# Experiment_2.net
KiCad netlist of a schematic drawn in Altium Designer
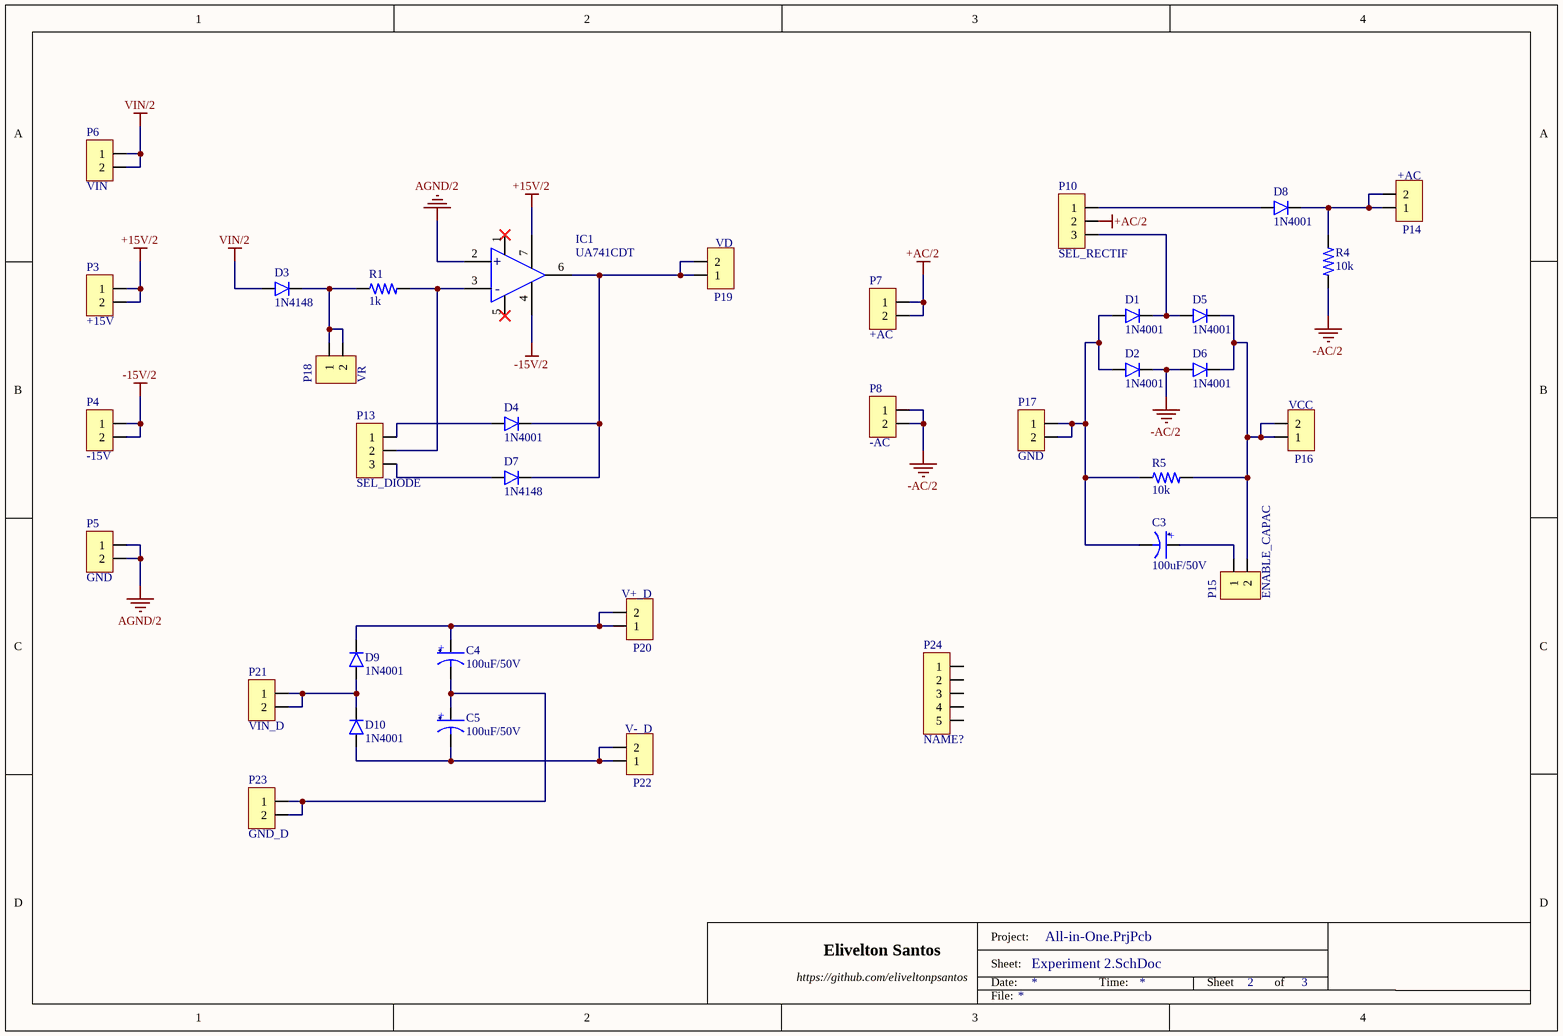
[diagram p0: Experiment 2.SchDoc]

(export (version "E")
  (design (tool "Eeschema 10.0.6"))
  (components
    (comp (ref "C3")
      (value "100uF/50V")
      (footprint "C-3.5x8")
      (description "CAP ALUM 100UF 20% 50V RADIAL")
      (fields
        (field (name "MANUFACTURER") "Nichicon")
        (field (name "MANUFACTURER PART NUMBER") "UVR1H101MPD")
      )
      (libsource (lib "Capacitors") (part "UVR1H101MPD"))
    )
    (comp (ref "C4")
      (value "100uF/50V")
      (footprint "C-3.5x8")
      (description "CAP ALUM 100UF 20% 50V RADIAL")
      (fields
        (field (name "MANUFACTURER") "Nichicon")
        (field (name "MANUFACTURER PART NUMBER") "UVR1H101MPD")
      )
      (libsource (lib "") (part "UVR1H101MPD_1"))
    )
    (comp (ref "C5")
      (value "100uF/50V")
      (footprint "C-3.5x8")
      (description "CAP ALUM 100UF 20% 50V RADIAL")
      (fields
        (field (name "MANUFACTURER") "Nichicon")
        (field (name "MANUFACTURER PART NUMBER") "UVR1H101MPD")
      )
      (libsource (lib "") (part "UVR1H101MPD_1"))
    )
    (comp (ref "D1")
      (value "1N4001")
      (footprint "DO41-10")
      (description "DIODE GEN PURP 50V 1A DO41")
      (fields (field (name "MANUFACTURER") "Fairchild Semiconductor"))
      (libsource (lib "Diodes") (part "1N4001"))
    )
    (comp (ref "D2")
      (value "1N4001")
      (footprint "DO41-10")
      (description "DIODE GEN PURP 50V 1A DO41")
      (fields (field (name "MANUFACTURER") "Fairchild Semiconductor"))
      (libsource (lib "Diodes") (part "1N4001"))
    )
    (comp (ref "D3")
      (value "1N4148")
      (footprint "DO35-10")
      (description "DIODE GEN PURP 100V 200MA DO35")
      (fields (field (name "MANUFACTURER") "Fairchild Semiconductor"))
      (libsource (lib "Diodes") (part "1N4148"))
    )
    (comp (ref "D4")
      (value "1N4001")
      (footprint "DO41-10")
      (description "DIODE GEN PURP 50V 1A DO41")
      (fields (field (name "MANUFACTURER") "Fairchild Semiconductor"))
      (libsource (lib "Diodes") (part "1N4001"))
    )
    (comp (ref "D5")
      (value "1N4001")
      (footprint "DO41-10")
      (description "DIODE GEN PURP 50V 1A DO41")
      (fields (field (name "MANUFACTURER") "Fairchild Semiconductor"))
      (libsource (lib "Diodes") (part "1N4001"))
    )
    (comp (ref "D6")
      (value "1N4001")
      (footprint "DO41-10")
      (description "DIODE GEN PURP 50V 1A DO41")
      (fields (field (name "MANUFACTURER") "Fairchild Semiconductor"))
      (libsource (lib "Diodes") (part "1N4001"))
    )
    (comp (ref "D7")
      (value "1N4148")
      (footprint "DO35-10")
      (description "DIODE GEN PURP 100V 200MA DO35")
      (fields (field (name "MANUFACTURER") "Fairchild Semiconductor"))
      (libsource (lib "Diodes") (part "1N4148"))
    )
    (comp (ref "D8")
      (value "1N4001")
      (footprint "DO41-10")
      (description "DIODE GEN PURP 50V 1A DO41")
      (fields (field (name "MANUFACTURER") "Fairchild Semiconductor"))
      (libsource (lib "Diodes") (part "1N4001"))
    )
    (comp (ref "D9")
      (value "1N4001")
      (footprint "DO41-10")
      (description "DIODE GEN PURP 50V 1A DO41")
      (fields (field (name "MANUFACTURER") "Fairchild Semiconductor"))
      (libsource (lib "Diodes") (part "1N4001"))
    )
    (comp (ref "D10")
      (value "1N4001")
      (footprint "DO41-10")
      (description "DIODE GEN PURP 50V 1A DO41")
      (fields (field (name "MANUFACTURER") "Fairchild Semiconductor"))
      (libsource (lib "Diodes") (part "1N4001"))
    )
    (comp (ref "IC1")
      (value "UA741CDT")
      (footprint "SOIC-8")
      (description "IC OPAMP GP 1MHZ 8SO")
      (fields (field (name "MANUFACTURER") "STMicroelectronics"))
      (libsource (lib "ICs") (part "UA741CDT"))
    )
    (comp (ref "P3")
      (value "+15V")
      (footprint "PINHD-1X02 ONCE")
      (description "CONN HEADER 2POS .100\" STR TIN")
      (fields
        (field (name "MANUFACTURER") "Molex, LLC")
        (field (name "MANUFACTURER PART NUMBER") "0901200122")
      )
      (libsource (lib "Connectors") (part "PIN HEADER 1X02 ONCE"))
    )
    (comp (ref "P4")
      (value "-15V")
      (footprint "PINHD-1X02 ONCE")
      (description "CONN HEADER 2POS .100\" STR TIN")
      (fields
        (field (name "MANUFACTURER") "Molex, LLC")
        (field (name "MANUFACTURER PART NUMBER") "0901200122")
      )
      (libsource (lib "Connectors") (part "PIN HEADER 1X02 ONCE"))
    )
    (comp (ref "P5")
      (value "GND")
      (footprint "PINHD-1X02 ONCE")
      (description "CONN HEADER 2POS .100\" STR TIN")
      (fields
        (field (name "MANUFACTURER") "Molex, LLC")
        (field (name "MANUFACTURER PART NUMBER") "0901200122")
      )
      (libsource (lib "Connectors") (part "PIN HEADER 1X02 ONCE"))
    )
    (comp (ref "P6")
      (value "VIN")
      (footprint "PINHD-1X02 ONCE")
      (description "CONN HEADER 2POS .100\" STR TIN")
      (fields
        (field (name "MANUFACTURER") "Molex, LLC")
        (field (name "MANUFACTURER PART NUMBER") "0901200122")
      )
      (libsource (lib "Connectors") (part "PIN HEADER 1X02 ONCE"))
    )
    (comp (ref "P7")
      (value "+AC")
      (footprint "PINHD-1X02 ONCE")
      (description "CONN HEADER 2POS .100\" STR TIN")
      (fields
        (field (name "MANUFACTURER") "Molex, LLC")
        (field (name "MANUFACTURER PART NUMBER") "0901200122")
      )
      (libsource (lib "Connectors") (part "PIN HEADER 1X02 ONCE"))
    )
    (comp (ref "P8")
      (value "-AC")
      (footprint "PINHD-1X02 ONCE")
      (description "CONN HEADER 2POS .100\" STR TIN")
      (fields
        (field (name "MANUFACTURER") "Molex, LLC")
        (field (name "MANUFACTURER PART NUMBER") "0901200122")
      )
      (libsource (lib "Connectors") (part "PIN HEADER 1X02 ONCE"))
    )
    (comp (ref "P10")
      (value "SEL_RECTIF")
      (footprint "PINHD-1X03")
      (description "CONN HEADER 3POS .100\" STR TIN")
      (fields
        (field (name "MANUFACTURER") "Molex, LLC")
        (field (name "MANUFACTURER PART NUMBER") "0901200123")
      )
      (libsource (lib "Connectors") (part "PIN HEADER 1X03"))
    )
    (comp (ref "P13")
      (value "SEL_DIODE")
      (footprint "PINHD-1X03")
      (description "CONN HEADER 3POS .100\" STR TIN")
      (fields
        (field (name "MANUFACTURER") "Molex, LLC")
        (field (name "MANUFACTURER PART NUMBER") "0901200123")
      )
      (libsource (lib "Connectors") (part "PIN HEADER 1X03"))
    )
    (comp (ref "P14")
      (value "+AC")
      (footprint "PINHD-1X02 ONCE")
      (description "CONN HEADER 2POS .100\" STR TIN")
      (fields
        (field (name "MANUFACTURER") "Molex, LLC")
        (field (name "MANUFACTURER PART NUMBER") "0901200122")
      )
      (libsource (lib "") (part "PIN HEADER 1X02 ONCE_1"))
    )
    (comp (ref "P15")
      (value "ENABLE_CAPAC")
      (footprint "PINHD-1X02")
      (description "CONN HEADER 2POS .100\" STR TIN")
      (fields
        (field (name "MANUFACTURER") "Molex, LLC")
        (field (name "MANUFACTURER PART NUMBER") "0901200122")
      )
      (libsource (lib "Connectors") (part "PIN HEADER 1X02"))
    )
    (comp (ref "P16")
      (value "VCC")
      (footprint "PINHD-1X02 ONCE")
      (description "CONN HEADER 2POS .100\" STR TIN")
      (fields
        (field (name "MANUFACTURER") "Molex, LLC")
        (field (name "MANUFACTURER PART NUMBER") "0901200122")
      )
      (libsource (lib "") (part "PIN HEADER 1X02 ONCE_1"))
    )
    (comp (ref "P17")
      (value "GND")
      (footprint "PINHD-1X02 ONCE")
      (description "CONN HEADER 2POS .100\" STR TIN")
      (fields
        (field (name "MANUFACTURER") "Molex, LLC")
        (field (name "MANUFACTURER PART NUMBER") "0901200122")
      )
      (libsource (lib "Connectors") (part "PIN HEADER 1X02 ONCE"))
    )
    (comp (ref "P18")
      (value "VR")
      (footprint "PINHD-1X02 ONCE")
      (description "CONN HEADER 2POS .100\" STR TIN")
      (fields
        (field (name "MANUFACTURER") "Molex, LLC")
        (field (name "MANUFACTURER PART NUMBER") "0901200122")
      )
      (libsource (lib "") (part "PIN HEADER 1X02 ONCE_2"))
    )
    (comp (ref "P19")
      (value "VD")
      (footprint "PINHD-1X02 ONCE")
      (description "CONN HEADER 2POS .100\" STR TIN")
      (fields
        (field (name "MANUFACTURER") "Molex, LLC")
        (field (name "MANUFACTURER PART NUMBER") "0901200122")
      )
      (libsource (lib "") (part "PIN HEADER 1X02 ONCE_1"))
    )
    (comp (ref "P20")
      (value "V+_D")
      (footprint "PINHD-1X02 ONCE")
      (description "CONN HEADER 2POS .100\" STR TIN")
      (fields
        (field (name "MANUFACTURER") "Molex, LLC")
        (field (name "MANUFACTURER PART NUMBER") "0901200122")
      )
      (libsource (lib "") (part "PIN HEADER 1X02 ONCE_1"))
    )
    (comp (ref "P21")
      (value "VIN_D")
      (footprint "PINHD-1X02 ONCE")
      (description "CONN HEADER 2POS .100\" STR TIN")
      (fields
        (field (name "MANUFACTURER") "Molex, LLC")
        (field (name "MANUFACTURER PART NUMBER") "0901200122")
      )
      (libsource (lib "Connectors") (part "PIN HEADER 1X02 ONCE"))
    )
    (comp (ref "P22")
      (value "V-_D")
      (footprint "PINHD-1X02 ONCE")
      (description "CONN HEADER 2POS .100\" STR TIN")
      (fields
        (field (name "MANUFACTURER") "Molex, LLC")
        (field (name "MANUFACTURER PART NUMBER") "0901200122")
      )
      (libsource (lib "") (part "PIN HEADER 1X02 ONCE_1"))
    )
    (comp (ref "P23")
      (value "GND_D")
      (footprint "PINHD-1X02 ONCE")
      (description "CONN HEADER 2POS .100\" STR TIN")
      (fields
        (field (name "MANUFACTURER") "Molex, LLC")
        (field (name "MANUFACTURER PART NUMBER") "0901200122")
      )
      (libsource (lib "Connectors") (part "PIN HEADER 1X02 ONCE"))
    )
    (comp (ref "P24")
      (value "NAME?")
      (footprint "PINHD-1X05")
      (description "CONN HEADER 5POS .100\" STR TIN")
      (fields
        (field (name "MANUFACTURER") "Molex, LLC")
        (field (name "MANUFACTURER PART NUMBER") "0901200125")
      )
      (libsource (lib "Connectors") (part "PIN HEADER 1X05"))
    )
    (comp (ref "R1")
      (value "1k")
      (footprint "R0805")
      (description "RES SMD 1K OHM 1% 1/8W 0805")
      (fields
        (field (name "MANUFACTURER") "Panasonic Electronic Components")
        (field (name "MANUFACTURER PART NUMBER") "ERJ-6ENF1001V")
      )
      (libsource (lib "Resistors") (part "ERJ-6ENF1001V"))
    )
    (comp (ref "R4")
      (value "10k")
      (footprint "R0805")
      (description "RES SMD 10K OHM 1% 1/8W 0805")
      (fields
        (field (name "MANUFACTURER") "Panasonic Electronic Components")
        (field (name "MANUFACTURER PART NUMBER") "ERJ-6ENF1002V")
      )
      (libsource (lib "Resistors") (part "ERJ-6ENF1002V"))
    )
    (comp (ref "R5")
      (value "10k")
      (footprint "R0805")
      (description "RES SMD 10K OHM 1% 1/8W 0805")
      (fields
        (field (name "MANUFACTURER") "Panasonic Electronic Components")
        (field (name "MANUFACTURER PART NUMBER") "ERJ-6ENF1002V")
      )
      (libsource (lib "Resistors") (part "ERJ-6ENF1002V"))
    )
  )
  (nets
    (net (code "1") (name "+15V{slash}2") (class "Default")
      (node (ref "IC1") (pin "7") (pinfunction "VCC+_7") (pintype "power_in"))
      (node (ref "P3") (pin "1") (pinfunction "1_1") (pintype "passive"))
      (node (ref "P3") (pin "2") (pinfunction "2_2") (pintype "passive"))
    )
    (net (code "2") (name "+AC{slash}2") (class "Default")
      (node (ref "P10") (pin "2") (pinfunction "2_2") (pintype "passive"))
      (node (ref "P7") (pin "1") (pinfunction "1_1") (pintype "passive"))
      (node (ref "P7") (pin "2") (pinfunction "2_2") (pintype "passive"))
    )
    (net (code "3") (name "-15V{slash}2") (class "Default")
      (node (ref "IC1") (pin "4") (pinfunction "VCC-_4") (pintype "power_in"))
      (node (ref "P4") (pin "1") (pinfunction "1_1") (pintype "passive"))
      (node (ref "P4") (pin "2") (pinfunction "2_2") (pintype "passive"))
    )
    (net (code "4") (name "-AC{slash}2") (class "Default")
      (node (ref "D2") (pin "C") (pinfunction "Cathode_C") (pintype "passive"))
      (node (ref "D6") (pin "A") (pinfunction "Anode_A") (pintype "passive"))
      (node (ref "P8") (pin "1") (pinfunction "1_1") (pintype "passive"))
      (node (ref "P8") (pin "2") (pinfunction "2_2") (pintype "passive"))
      (node (ref "R4") (pin "1") (pinfunction "1_1") (pintype "passive"))
    )
    (net (code "5") (name "AGND{slash}2") (class "Default")
      (node (ref "IC1") (pin "2") (pinfunction "-_2") (pintype "passive"))
      (node (ref "P5") (pin "1") (pinfunction "1_1") (pintype "passive"))
      (node (ref "P5") (pin "2") (pinfunction "2_2") (pintype "passive"))
    )
    (net (code "6") (name "Net-(C3-+)") (class "Default")
      (node (ref "C3") (pin "1") (pinfunction "+_1") (pintype "passive"))
      (node (ref "P15") (pin "1") (pinfunction "1_1") (pintype "passive"))
    )
    (net (code "7") (name "Net-(C3--)") (class "Default")
      (node (ref "C3") (pin "2") (pinfunction "-_2") (pintype "passive"))
      (node (ref "D1") (pin "A") (pinfunction "Anode_A") (pintype "passive"))
      (node (ref "D2") (pin "A") (pinfunction "Anode_A") (pintype "passive"))
      (node (ref "P17") (pin "1") (pinfunction "1_1") (pintype "passive"))
      (node (ref "P17") (pin "2") (pinfunction "2_2") (pintype "passive"))
      (node (ref "R5") (pin "1") (pinfunction "1_1") (pintype "passive"))
    )
    (net (code "8") (name "Net-(C4-+)") (class "Default")
      (node (ref "C4") (pin "1") (pinfunction "+_1") (pintype "passive"))
      (node (ref "D9") (pin "C") (pinfunction "Cathode_C") (pintype "passive"))
      (node (ref "P20") (pin "1") (pinfunction "1_1") (pintype "passive"))
      (node (ref "P20") (pin "2") (pinfunction "2_2") (pintype "passive"))
    )
    (net (code "9") (name "Net-(C4--)") (class "Default")
      (node (ref "C4") (pin "2") (pinfunction "-_2") (pintype "passive"))
      (node (ref "C5") (pin "1") (pinfunction "+_1") (pintype "passive"))
      (node (ref "P23") (pin "1") (pinfunction "1_1") (pintype "passive"))
      (node (ref "P23") (pin "2") (pinfunction "2_2") (pintype "passive"))
    )
    (net (code "10") (name "Net-(C5--)") (class "Default")
      (node (ref "C5") (pin "2") (pinfunction "-_2") (pintype "passive"))
      (node (ref "D10") (pin "A") (pinfunction "Anode_A") (pintype "passive"))
      (node (ref "P22") (pin "1") (pinfunction "1_1") (pintype "passive"))
      (node (ref "P22") (pin "2") (pinfunction "2_2") (pintype "passive"))
    )
    (net (code "11") (name "Net-(D1-Cathode)") (class "Default")
      (node (ref "D1") (pin "C") (pinfunction "Cathode_C") (pintype "passive"))
      (node (ref "D5") (pin "A") (pinfunction "Anode_A") (pintype "passive"))
      (node (ref "P10") (pin "3") (pinfunction "3_3") (pintype "passive"))
    )
    (net (code "12") (name "Net-(D3-Cathode)") (class "Default")
      (node (ref "D3") (pin "C") (pinfunction "Cathode_C") (pintype "passive"))
      (node (ref "P18") (pin "1") (pinfunction "1_1") (pintype "passive"))
      (node (ref "P18") (pin "2") (pinfunction "2_2") (pintype "passive"))
      (node (ref "R1") (pin "1") (pinfunction "1_1") (pintype "passive"))
    )
    (net (code "13") (name "Net-(D4-Anode)") (class "Default")
      (node (ref "D4") (pin "A") (pinfunction "Anode_A") (pintype "passive"))
      (node (ref "P13") (pin "1") (pinfunction "1_1") (pintype "passive"))
    )
    (net (code "14") (name "Net-(D4-Cathode)") (class "Default")
      (node (ref "D4") (pin "C") (pinfunction "Cathode_C") (pintype "passive"))
      (node (ref "D7") (pin "C") (pinfunction "Cathode_C") (pintype "passive"))
      (node (ref "IC1") (pin "6") (pinfunction "OUTPUT_6") (pintype "passive"))
      (node (ref "P19") (pin "1") (pinfunction "1_1") (pintype "passive"))
      (node (ref "P19") (pin "2") (pinfunction "2_2") (pintype "passive"))
    )
    (net (code "15") (name "Net-(D5-Cathode)") (class "Default")
      (node (ref "D5") (pin "C") (pinfunction "Cathode_C") (pintype "passive"))
      (node (ref "D6") (pin "C") (pinfunction "Cathode_C") (pintype "passive"))
      (node (ref "P15") (pin "2") (pinfunction "2_2") (pintype "passive"))
      (node (ref "P16") (pin "1") (pinfunction "1_1") (pintype "passive"))
      (node (ref "P16") (pin "2") (pinfunction "2_2") (pintype "passive"))
      (node (ref "R5") (pin "2") (pinfunction "2_2") (pintype "passive"))
    )
    (net (code "16") (name "Net-(D7-Anode)") (class "Default")
      (node (ref "D7") (pin "A") (pinfunction "Anode_A") (pintype "passive"))
      (node (ref "P13") (pin "3") (pinfunction "3_3") (pintype "passive"))
    )
    (net (code "17") (name "Net-(D8-Anode)") (class "Default")
      (node (ref "D8") (pin "A") (pinfunction "Anode_A") (pintype "passive"))
      (node (ref "P10") (pin "1") (pinfunction "1_1") (pintype "passive"))
    )
    (net (code "18") (name "Net-(D8-Cathode)") (class "Default")
      (node (ref "D8") (pin "C") (pinfunction "Cathode_C") (pintype "passive"))
      (node (ref "P14") (pin "1") (pinfunction "1_1") (pintype "passive"))
      (node (ref "P14") (pin "2") (pinfunction "2_2") (pintype "passive"))
      (node (ref "R4") (pin "2") (pinfunction "2_2") (pintype "passive"))
    )
    (net (code "19") (name "Net-(D10-Cathode)") (class "Default")
      (node (ref "D10") (pin "C") (pinfunction "Cathode_C") (pintype "passive"))
      (node (ref "D9") (pin "A") (pinfunction "Anode_A") (pintype "passive"))
      (node (ref "P21") (pin "1") (pinfunction "1_1") (pintype "passive"))
      (node (ref "P21") (pin "2") (pinfunction "2_2") (pintype "passive"))
    )
    (net (code "20") (name "Net-(IC1-+)") (class "Default")
      (node (ref "IC1") (pin "3") (pinfunction "+_3") (pintype "passive"))
      (node (ref "P13") (pin "2") (pinfunction "2_2") (pintype "passive"))
      (node (ref "R1") (pin "2") (pinfunction "2_2") (pintype "passive"))
    )
    (net (code "21") (name "VIN{slash}2") (class "Default")
      (node (ref "D3") (pin "A") (pinfunction "Anode_A") (pintype "passive"))
      (node (ref "P6") (pin "1") (pinfunction "1_1") (pintype "passive"))
      (node (ref "P6") (pin "2") (pinfunction "2_2") (pintype "passive"))
    )
    (net (code "22") (name "unconnected-(IC1-OFFSET1-Pad1)") (class "Default")
      (node (ref "IC1") (pin "1") (pinfunction "OFFSET1_1") (pintype "passive+no_connect"))
    )
    (net (code "23") (name "unconnected-(IC1-OFFSET2-Pad5)") (class "Default")
      (node (ref "IC1") (pin "5") (pinfunction "OFFSET2_5") (pintype "passive+no_connect"))
    )
    (net (code "24") (name "unconnected-(P24-Pad1)") (class "Default")
      (node (ref "P24") (pin "1") (pinfunction "1_1") (pintype "passive"))
    )
    (net (code "25") (name "unconnected-(P24-Pad2)") (class "Default")
      (node (ref "P24") (pin "2") (pinfunction "2_2") (pintype "passive"))
    )
    (net (code "26") (name "unconnected-(P24-Pad3)") (class "Default")
      (node (ref "P24") (pin "3") (pinfunction "3_3") (pintype "passive"))
    )
    (net (code "27") (name "unconnected-(P24-Pad4)") (class "Default")
      (node (ref "P24") (pin "4") (pinfunction "4_4") (pintype "passive"))
    )
    (net (code "28") (name "unconnected-(P24-Pad5)") (class "Default")
      (node (ref "P24") (pin "5") (pinfunction "5_5") (pintype "passive"))
    )
  )
)
